# RS485_Mayfly.net
KiCad netlist of a schematic drawn in EAGLE
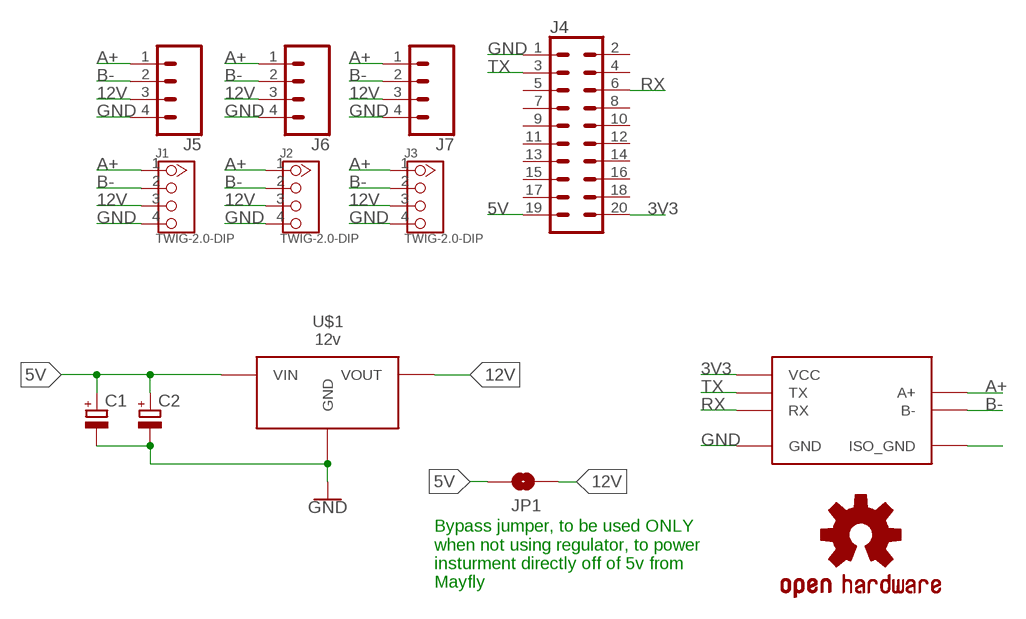
[diagram p0: schematic, sheet 1]

(export (version "E")
  (design (tool "Eeschema 10.0.6"))
  (components
    (comp (ref "C1")
      (value "CPOL-EUE2,5-6E")
      (footprint "eagle-import:E2,5-6E")
      (libsource (lib "eagle-import") (part "CPOL-EUE2,5-6E"))
    )
    (comp (ref "C2")
      (value "CPOL-EUE2,5-6E")
      (footprint "eagle-import:E2,5-6E")
      (libsource (lib "eagle-import") (part "CPOL-EUE2,5-6E"))
    )
    (comp (ref "J1")
      (value "TWIG-2.0-DIP")
      (footprint "eagle-import:2.0_1X4")
      (libsource (lib "eagle-import") (part "TWIG-2.0-DIP"))
    )
    (comp (ref "J2")
      (value "TWIG-2.0-DIP")
      (footprint "eagle-import:2.0_1X4")
      (libsource (lib "eagle-import") (part "TWIG-2.0-DIP"))
    )
    (comp (ref "J3")
      (value "TWIG-2.0-DIP")
      (footprint "eagle-import:2.0_1X4")
      (libsource (lib "eagle-import") (part "TWIG-2.0-DIP"))
    )
    (comp (ref "J4")
      (value "CONN_10X2")
      (footprint "eagle-import:2X10")
      (libsource (lib "eagle-import") (part "CONN_10X2"))
    )
    (comp (ref "J5")
      (value "CONN_42.54_NOSILK")
      (footprint "eagle-import:1X04_NOSILK")
      (libsource (lib "eagle-import") (part "CONN_42.54_NOSILK"))
    )
    (comp (ref "J6")
      (value "CONN_42.54_NOSILK")
      (footprint "eagle-import:1X04_NOSILK")
      (libsource (lib "eagle-import") (part "CONN_42.54_NOSILK"))
    )
    (comp (ref "J7")
      (value "CONN_42.54_NOSILK")
      (footprint "eagle-import:1X04_NOSILK")
      (libsource (lib "eagle-import") (part "CONN_42.54_NOSILK"))
    )
    (comp (ref "JP1")
      (value "JUMPER-SMT_2_NO_SILK")
      (footprint "eagle-import:SMT-JUMPER_2_NO_SILK")
      (libsource (lib "eagle-import") (part "JUMPER-SMT_2_NO_SILK"))
    )
    (comp (ref "LOGO1")
      (value "OSHW-LOGOMINI")
      (footprint "eagle-import:OSHW-LOGO-MINI")
      (libsource (lib "eagle-import") (part "OSHW-LOGOMINI"))
    )
    (comp (ref "U$1")
      (value "12v")
      (footprint "eagle-import:POLOLU_REG")
      (libsource (lib "eagle-import") (part "POLOLU_VREG"))
    )
    (comp (ref "U$2")
      (value "SMC_RS485")
      (footprint "eagle-import:SMC_RS485")
      (libsource (lib "eagle-import") (part "SMC_RS485"))
    )
  )
  (nets
    (net (code "1") (name "/3V3") (class "Default")
      (node (ref "J4") (pin "20") (pinfunction "20_20") (pintype "passive"))
      (node (ref "U$2") (pin "VCC") (pinfunction "VCC_VCC") (pintype "bidirectional"))
    )
    (net (code "2") (name "/A+") (class "Default")
      (node (ref "J1") (pin "1") (pinfunction "1_1") (pintype "bidirectional"))
      (node (ref "J2") (pin "1") (pinfunction "1_1") (pintype "bidirectional"))
      (node (ref "J3") (pin "1") (pinfunction "1_1") (pintype "bidirectional"))
      (node (ref "J5") (pin "1") (pinfunction "1_1") (pintype "passive"))
      (node (ref "J6") (pin "1") (pinfunction "1_1") (pintype "passive"))
      (node (ref "J7") (pin "1") (pinfunction "1_1") (pintype "passive"))
      (node (ref "U$2") (pin "A+") (pinfunction "A+_A+") (pintype "bidirectional"))
    )
    (net (code "3") (name "/B-") (class "Default")
      (node (ref "J1") (pin "2") (pinfunction "2_2") (pintype "bidirectional"))
      (node (ref "J2") (pin "2") (pinfunction "2_2") (pintype "bidirectional"))
      (node (ref "J3") (pin "2") (pinfunction "2_2") (pintype "bidirectional"))
      (node (ref "J5") (pin "2") (pinfunction "2_2") (pintype "passive"))
      (node (ref "J6") (pin "2") (pinfunction "2_2") (pintype "passive"))
      (node (ref "J7") (pin "2") (pinfunction "2_2") (pintype "passive"))
      (node (ref "U$2") (pin "B-") (pinfunction "B-_B-") (pintype "bidirectional"))
    )
    (net (code "4") (name "/RX") (class "Default")
      (node (ref "J4") (pin "6") (pinfunction "6_6") (pintype "passive"))
      (node (ref "U$2") (pin "RX") (pinfunction "RX_RX") (pintype "bidirectional"))
    )
    (net (code "5") (name "/TX") (class "Default")
      (node (ref "J4") (pin "3") (pinfunction "3_3") (pintype "passive"))
      (node (ref "U$2") (pin "TX") (pinfunction "TX_TX") (pintype "bidirectional"))
    )
    (net (code "6") (name "5V") (class "Default")
      (node (ref "C1") (pin "+") (pinfunction "+_+") (pintype "passive"))
      (node (ref "C2") (pin "+") (pinfunction "+_+") (pintype "passive"))
      (node (ref "J4") (pin "19") (pinfunction "19_19") (pintype "passive"))
      (node (ref "JP1") (pin "2") (pinfunction "2_2") (pintype "passive"))
      (node (ref "U$1") (pin "VIN") (pinfunction "VIN_VIN") (pintype "bidirectional"))
    )
    (net (code "7") (name "12V") (class "Default")
      (node (ref "J1") (pin "3") (pinfunction "3_3") (pintype "bidirectional"))
      (node (ref "J2") (pin "3") (pinfunction "3_3") (pintype "bidirectional"))
      (node (ref "J3") (pin "3") (pinfunction "3_3") (pintype "bidirectional"))
      (node (ref "J5") (pin "3") (pinfunction "3_3") (pintype "passive"))
      (node (ref "J6") (pin "3") (pinfunction "3_3") (pintype "passive"))
      (node (ref "J7") (pin "3") (pinfunction "3_3") (pintype "passive"))
      (node (ref "JP1") (pin "1") (pinfunction "1_1") (pintype "passive"))
      (node (ref "U$1") (pin "VOUT") (pinfunction "VOUT_VOUT") (pintype "bidirectional"))
    )
    (net (code "8") (name "GND") (class "Default")
      (node (ref "C1") (pin "-") (pinfunction "-_-") (pintype "passive"))
      (node (ref "C2") (pin "-") (pinfunction "-_-") (pintype "passive"))
      (node (ref "J1") (pin "4") (pinfunction "4_4") (pintype "bidirectional"))
      (node (ref "J2") (pin "4") (pinfunction "4_4") (pintype "bidirectional"))
      (node (ref "J3") (pin "4") (pinfunction "4_4") (pintype "bidirectional"))
      (node (ref "J4") (pin "1") (pinfunction "1_1") (pintype "passive"))
      (node (ref "J5") (pin "4") (pinfunction "4_4") (pintype "passive"))
      (node (ref "J6") (pin "4") (pinfunction "4_4") (pintype "passive"))
      (node (ref "J7") (pin "4") (pinfunction "4_4") (pintype "passive"))
      (node (ref "U$1") (pin "GND") (pinfunction "GND_GND") (pintype "bidirectional"))
      (node (ref "U$2") (pin "GND") (pinfunction "GND_GND") (pintype "bidirectional"))
    )
    (net (code "9") (name "unconnected-(J4-Pad2)") (class "Default")
      (node (ref "J4") (pin "2") (pinfunction "2_2") (pintype "passive"))
    )
    (net (code "10") (name "unconnected-(J4-Pad4)") (class "Default")
      (node (ref "J4") (pin "4") (pinfunction "4_4") (pintype "passive"))
    )
    (net (code "11") (name "unconnected-(J4-Pad5)") (class "Default")
      (node (ref "J4") (pin "5") (pinfunction "5_5") (pintype "passive"))
    )
    (net (code "12") (name "unconnected-(J4-Pad7)") (class "Default")
      (node (ref "J4") (pin "7") (pinfunction "7_7") (pintype "passive"))
    )
    (net (code "13") (name "unconnected-(J4-Pad8)") (class "Default")
      (node (ref "J4") (pin "8") (pinfunction "8_8") (pintype "passive"))
    )
    (net (code "14") (name "unconnected-(J4-Pad9)") (class "Default")
      (node (ref "J4") (pin "9") (pinfunction "9_9") (pintype "passive"))
    )
    (net (code "15") (name "unconnected-(J4-Pad10)") (class "Default")
      (node (ref "J4") (pin "10") (pinfunction "10_10") (pintype "passive"))
    )
    (net (code "16") (name "unconnected-(J4-Pad11)") (class "Default")
      (node (ref "J4") (pin "11") (pinfunction "11_11") (pintype "passive"))
    )
    (net (code "17") (name "unconnected-(J4-Pad12)") (class "Default")
      (node (ref "J4") (pin "12") (pinfunction "12_12") (pintype "passive"))
    )
    (net (code "18") (name "unconnected-(J4-Pad13)") (class "Default")
      (node (ref "J4") (pin "13") (pinfunction "13_13") (pintype "passive"))
    )
    (net (code "19") (name "unconnected-(J4-Pad14)") (class "Default")
      (node (ref "J4") (pin "14") (pinfunction "14_14") (pintype "passive"))
    )
    (net (code "20") (name "unconnected-(J4-Pad15)") (class "Default")
      (node (ref "J4") (pin "15") (pinfunction "15_15") (pintype "passive"))
    )
    (net (code "21") (name "unconnected-(J4-Pad16)") (class "Default")
      (node (ref "J4") (pin "16") (pinfunction "16_16") (pintype "passive"))
    )
    (net (code "22") (name "unconnected-(J4-Pad17)") (class "Default")
      (node (ref "J4") (pin "17") (pinfunction "17_17") (pintype "passive"))
    )
    (net (code "23") (name "unconnected-(J4-Pad18)") (class "Default")
      (node (ref "J4") (pin "18") (pinfunction "18_18") (pintype "passive"))
    )
    (net (code "24") (name "unconnected-(U$2-ISO_GND-PadGND_ISO)") (class "Default")
      (node (ref "U$2") (pin "GND_ISO") (pinfunction "ISO_GND_GND_ISO") (pintype "bidirectional"))
    )
  )
)
